# combined.net
KiCad netlist of a schematic drawn in EAGLE
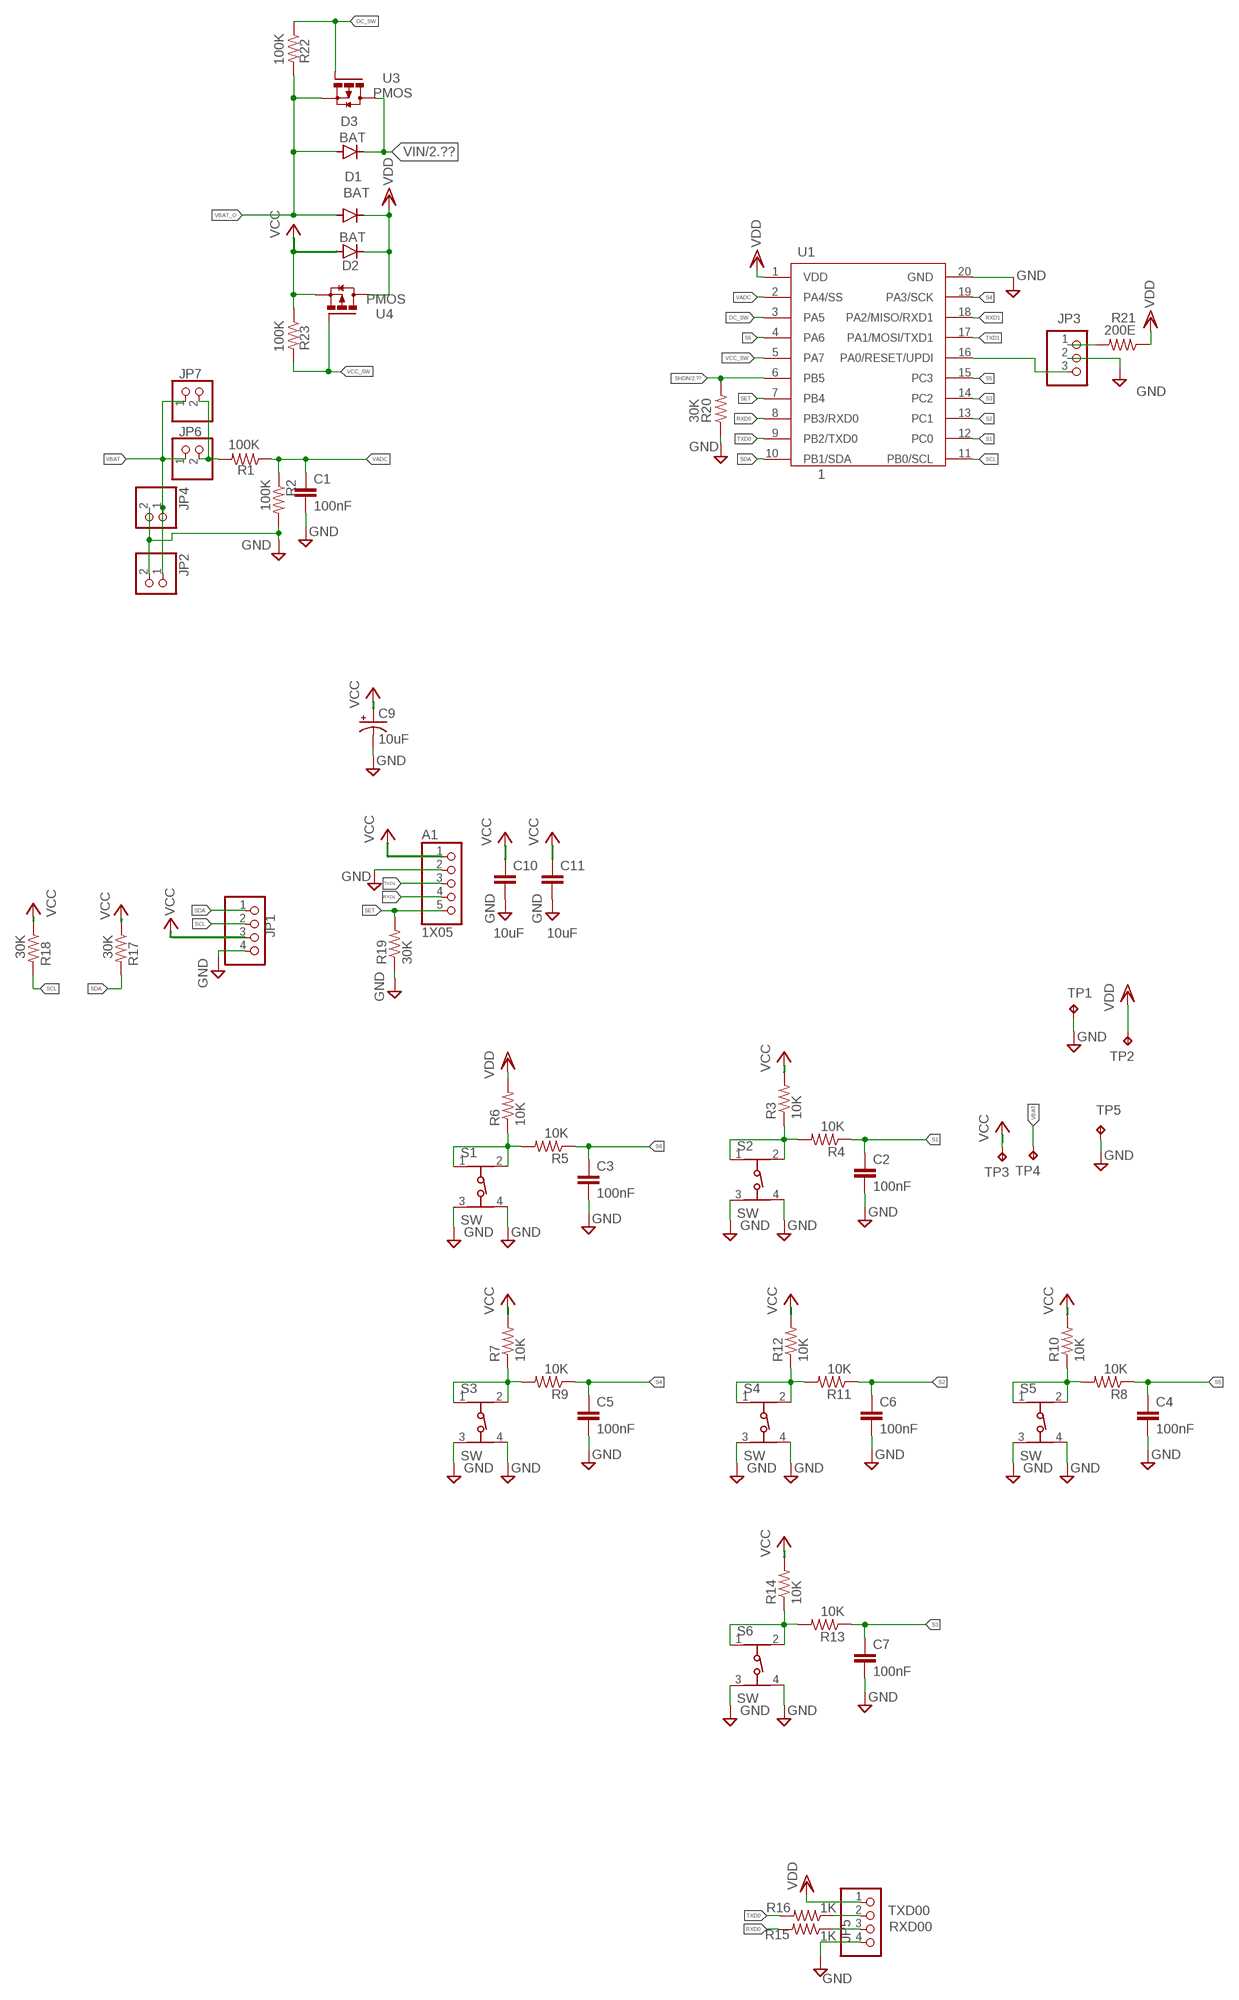
[diagram p0: schematic, sheet 1]
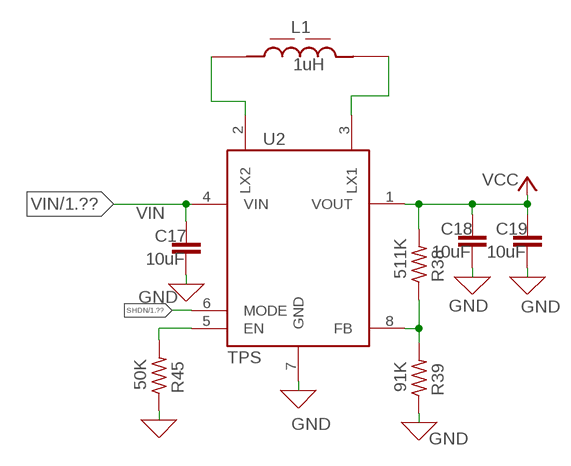
[diagram p1: schematic, sheet 2]

(export (version "E")
  (design (tool "Eeschema 10.0.6"))
  (components
    (comp (ref "C17")
      (value "10uF")
      (footprint "eagle-import:C0805")
      (libsource (lib "eagle-import") (part "C-EUC0805"))
    )
    (comp (ref "C18")
      (value "10uF")
      (footprint "eagle-import:C0805")
      (libsource (lib "eagle-import") (part "C-EUC0805"))
    )
    (comp (ref "C19")
      (value "10uF")
      (footprint "eagle-import:C0805")
      (libsource (lib "eagle-import") (part "C-EUC0805"))
    )
    (comp (ref "L1")
      (value "1uH")
      (footprint "eagle-import:IND_74404043220A")
      (fields (field (name "MF") "Wurth Electronics") (field (name "MP") "74404043220A"))
      (libsource (lib "eagle-import") (part "5040_INDUCTOR"))
    )
    (comp (ref "R38")
      (value "511K")
      (footprint "eagle-import:M0805")
      (libsource (lib "eagle-import") (part "R-US_M0805"))
    )
    (comp (ref "R39")
      (value "91K")
      (footprint "eagle-import:M0805")
      (libsource (lib "eagle-import") (part "R-US_M0805"))
    )
    (comp (ref "R45")
      (value "50K")
      (footprint "eagle-import:M0805")
      (libsource (lib "eagle-import") (part "R-US_M0805"))
    )
    (comp (ref "U2")
      (value "TPS")
      (footprint "eagle-import:SOTFL50P160X60-8N")
      (fields (field (name "MF") "Texas Instruments") (field (name "MP") "TPS563212DRLR"))
      (libsource (lib "eagle-import") (part "TPS563212DRLR"))
    )
    (comp (ref "A1")
      (value "1X05")
      (footprint "eagle-import:1X05X254")
      (libsource (lib "eagle-import") (part "1X05"))
    )
    (comp (ref "C1")
      (value "100nF")
      (footprint "eagle-import:C0805")
      (libsource (lib "eagle-import") (part "C-EUC0805"))
    )
    (comp (ref "C2")
      (value "100nF")
      (footprint "eagle-import:C0805")
      (libsource (lib "eagle-import") (part "C-EUC0805"))
    )
    (comp (ref "C3")
      (value "100nF")
      (footprint "eagle-import:C0805")
      (libsource (lib "eagle-import") (part "C-EUC0805"))
    )
    (comp (ref "C4")
      (value "100nF")
      (footprint "eagle-import:C0805")
      (libsource (lib "eagle-import") (part "C-EUC0805"))
    )
    (comp (ref "C5")
      (value "100nF")
      (footprint "eagle-import:C0805")
      (libsource (lib "eagle-import") (part "C-EUC0805"))
    )
    (comp (ref "C6")
      (value "100nF")
      (footprint "eagle-import:C0805")
      (libsource (lib "eagle-import") (part "C-EUC0805"))
    )
    (comp (ref "C7")
      (value "100nF")
      (footprint "eagle-import:C0805")
      (libsource (lib "eagle-import") (part "C-EUC0805"))
    )
    (comp (ref "C9")
      (value "10uF")
      (footprint "eagle-import:CT3528")
      (libsource (lib "eagle-import") (part "CPOL-USCT3528"))
    )
    (comp (ref "C10")
      (value "10uF")
      (footprint "eagle-import:C0805")
      (libsource (lib "eagle-import") (part "C-EUC0805"))
    )
    (comp (ref "C11")
      (value "10uF")
      (footprint "eagle-import:C0805")
      (libsource (lib "eagle-import") (part "C-EUC0805"))
    )
    (comp (ref "D1")
      (value "BAT")
      (footprint "eagle-import:SOD-123_MINI-SMA")
      (libsource (lib "eagle-import") (part "CGRM400-G5"))
    )
    (comp (ref "D2")
      (value "BAT")
      (footprint "eagle-import:SOD-123_MINI-SMA")
      (libsource (lib "eagle-import") (part "CGRM400-G5"))
    )
    (comp (ref "D3")
      (value "BAT")
      (footprint "eagle-import:SOD-123_MINI-SMA")
      (libsource (lib "eagle-import") (part "CGRM400-G5"))
    )
    (comp (ref "JP1")
      (value "PINHD-1X04_2.54-S")
      (footprint "eagle-import:1X04-S")
      (libsource (lib "eagle-import") (part "PINHD-1X04_2.54-S"))
    )
    (comp (ref "JP2")
      (value "PINHD-1X02_2.54-S")
      (footprint "eagle-import:1X02-S")
      (libsource (lib "eagle-import") (part "PINHD-1X02_2.54-S"))
    )
    (comp (ref "JP3")
      (value "PINHD-1X03_2.54-S")
      (footprint "eagle-import:1X03-S")
      (libsource (lib "eagle-import") (part "PINHD-1X03_2.54-S"))
    )
    (comp (ref "JP4")
      (value "PINHD-1X02_2.54-S")
      (footprint "eagle-import:1X02-S")
      (libsource (lib "eagle-import") (part "PINHD-1X02_2.54-S"))
    )
    (comp (ref "JP5")
      (value "PINHD-1X04_2.54-S")
      (footprint "eagle-import:1X04-S")
      (libsource (lib "eagle-import") (part "PINHD-1X04_2.54-S"))
    )
    (comp (ref "JP6")
      (value "PINHD-1X02_2.54-S")
      (footprint "eagle-import:1X02-S")
      (libsource (lib "eagle-import") (part "PINHD-1X02_2.54-S"))
    )
    (comp (ref "JP7")
      (value "PINHD-1X02_2.54-S")
      (footprint "eagle-import:1X02-S")
      (libsource (lib "eagle-import") (part "PINHD-1X02_2.54-S"))
    )
    (comp (ref "R1")
      (value "100K")
      (footprint "eagle-import:R0805")
      (libsource (lib "eagle-import") (part "R-US_R0805"))
    )
    (comp (ref "R2")
      (value "100K")
      (footprint "eagle-import:R0805")
      (libsource (lib "eagle-import") (part "R-US_R0805"))
    )
    (comp (ref "R3")
      (value "10K")
      (footprint "eagle-import:R0805")
      (libsource (lib "eagle-import") (part "R-US_R0805"))
    )
    (comp (ref "R4")
      (value "10K")
      (footprint "eagle-import:R0805")
      (libsource (lib "eagle-import") (part "R-US_R0805"))
    )
    (comp (ref "R5")
      (value "10K")
      (footprint "eagle-import:R0805")
      (libsource (lib "eagle-import") (part "R-US_R0805"))
    )
    (comp (ref "R6")
      (value "10K")
      (footprint "eagle-import:R0805")
      (libsource (lib "eagle-import") (part "R-US_R0805"))
    )
    (comp (ref "R7")
      (value "10K")
      (footprint "eagle-import:R0805")
      (libsource (lib "eagle-import") (part "R-US_R0805"))
    )
    (comp (ref "R8")
      (value "10K")
      (footprint "eagle-import:R0805")
      (libsource (lib "eagle-import") (part "R-US_R0805"))
    )
    (comp (ref "R9")
      (value "10K")
      (footprint "eagle-import:R0805")
      (libsource (lib "eagle-import") (part "R-US_R0805"))
    )
    (comp (ref "R10")
      (value "10K")
      (footprint "eagle-import:R0805")
      (libsource (lib "eagle-import") (part "R-US_R0805"))
    )
    (comp (ref "R11")
      (value "10K")
      (footprint "eagle-import:R0805")
      (libsource (lib "eagle-import") (part "R-US_R0805"))
    )
    (comp (ref "R12")
      (value "10K")
      (footprint "eagle-import:R0805")
      (libsource (lib "eagle-import") (part "R-US_R0805"))
    )
    (comp (ref "R13")
      (value "10K")
      (footprint "eagle-import:R0805")
      (libsource (lib "eagle-import") (part "R-US_R0805"))
    )
    (comp (ref "R14")
      (value "10K")
      (footprint "eagle-import:R0805")
      (libsource (lib "eagle-import") (part "R-US_R0805"))
    )
    (comp (ref "R15")
      (value "1K")
      (footprint "eagle-import:R0805")
      (libsource (lib "eagle-import") (part "R-US_R0805"))
    )
    (comp (ref "R16")
      (value "1K")
      (footprint "eagle-import:R0805")
      (libsource (lib "eagle-import") (part "R-US_R0805"))
    )
    (comp (ref "R17")
      (value "30K")
      (footprint "eagle-import:R0805")
      (libsource (lib "eagle-import") (part "R-US_R0805"))
    )
    (comp (ref "R18")
      (value "30K")
      (footprint "eagle-import:R0805")
      (libsource (lib "eagle-import") (part "R-US_R0805"))
    )
    (comp (ref "R19")
      (value "30K")
      (footprint "eagle-import:R0805")
      (libsource (lib "eagle-import") (part "R-US_R0805"))
    )
    (comp (ref "R20")
      (value "30K")
      (footprint "eagle-import:R0805")
      (libsource (lib "eagle-import") (part "R-US_R0805"))
    )
    (comp (ref "R21")
      (value "200E")
      (footprint "eagle-import:R0805")
      (libsource (lib "eagle-import") (part "R-US_R0805"))
    )
    (comp (ref "R22")
      (value "100K")
      (footprint "eagle-import:R0805")
      (libsource (lib "eagle-import") (part "R-US_R0805"))
    )
    (comp (ref "R23")
      (value "100K")
      (footprint "eagle-import:R0805")
      (libsource (lib "eagle-import") (part "R-US_R0805"))
    )
    (comp (ref "S1")
      (value "SW")
      (footprint "eagle-import:SW_55MM")
      (fields (field (name "MF") "C&K") (field (name "MP") "PTS 647 SK38 SMTR2 LFS"))
      (libsource (lib "eagle-import") (part "SW_55MM"))
    )
    (comp (ref "S2")
      (value "SW")
      (footprint "eagle-import:SW_55MM")
      (fields (field (name "MF") "C&K") (field (name "MP") "PTS 647 SK38 SMTR2 LFS"))
      (libsource (lib "eagle-import") (part "SW_55MM"))
    )
    (comp (ref "S3")
      (value "SW")
      (footprint "eagle-import:SW_55MM")
      (fields (field (name "MF") "C&K") (field (name "MP") "PTS 647 SK38 SMTR2 LFS"))
      (libsource (lib "eagle-import") (part "SW_55MM"))
    )
    (comp (ref "S4")
      (value "SW")
      (footprint "eagle-import:SW_55MM")
      (fields (field (name "MF") "C&K") (field (name "MP") "PTS 647 SK38 SMTR2 LFS"))
      (libsource (lib "eagle-import") (part "SW_55MM"))
    )
    (comp (ref "S5")
      (value "SW")
      (footprint "eagle-import:SW_55MM")
      (fields (field (name "MF") "C&K") (field (name "MP") "PTS 647 SK38 SMTR2 LFS"))
      (libsource (lib "eagle-import") (part "SW_55MM"))
    )
    (comp (ref "S6")
      (value "SW")
      (footprint "eagle-import:SW_55MM")
      (fields (field (name "MF") "C&K") (field (name "MP") "PTS 647 SK38 SMTR2 LFS"))
      (libsource (lib "eagle-import") (part "SW_55MM"))
    )
    (comp (ref "TP1")
      (value "GND")
      (footprint "eagle-import:TP18R")
      (libsource (lib "eagle-import") (part "TPTP18R"))
    )
    (comp (ref "TP2")
      (value "VDD")
      (footprint "eagle-import:TP18R")
      (libsource (lib "eagle-import") (part "TPTP18R"))
    )
    (comp (ref "TP3")
      (value "VCC")
      (footprint "eagle-import:TP18R")
      (libsource (lib "eagle-import") (part "TPTP18R"))
    )
    (comp (ref "TP4")
      (value "VBAT")
      (footprint "eagle-import:TP18R")
      (libsource (lib "eagle-import") (part "TPTP18R"))
    )
    (comp (ref "TP5")
      (value "GND")
      (footprint "eagle-import:TP18R")
      (libsource (lib "eagle-import") (part "TPTP18R"))
    )
    (comp (ref "U1")
      (value "1")
      (footprint "eagle-import:SOIC127P1032X265-20N")
      (fields (field (name "MF") "Microchip Technology") (field (name "MP") "ATTINY1616-SNR"))
      (libsource (lib "eagle-import") (part "ATTINY1616-SNR"))
    )
    (comp (ref "U3")
      (value "PMOS")
      (footprint "eagle-import:SOT103P240X110-3N")
      (fields (field (name "MF") "Diodes Inc.") (field (name "MP") "DMP3130L-7"))
      (libsource (lib "eagle-import") (part "DMP3165L"))
    )
    (comp (ref "U4")
      (value "PMOS")
      (footprint "eagle-import:SOT103P240X110-3N")
      (fields (field (name "MF") "Diodes Inc.") (field (name "MP") "DMP3130L-7"))
      (libsource (lib "eagle-import") (part "DMP3165L"))
    )
  )
  (nets
    (net (code "1") (name "DC_SW") (class "Default")
      (node (ref "R22") (pin "1") (pinfunction "1_1") (pintype "passive"))
      (node (ref "U1") (pin "3") (pinfunction "PA5_3") (pintype "bidirectional"))
      (node (ref "U3") (pin "1") (pinfunction "G_1") (pintype "passive"))
    )
    (net (code "2") (name "GND") (class "Default")
      (node (ref "A1") (pin "2") (pinfunction "2_2") (pintype "passive"))
      (node (ref "C1") (pin "2") (pinfunction "2_2") (pintype "passive"))
      (node (ref "C10") (pin "2") (pinfunction "2_2") (pintype "passive"))
      (node (ref "C11") (pin "2") (pinfunction "2_2") (pintype "passive"))
      (node (ref "C17") (pin "2") (pinfunction "2_2") (pintype "passive"))
      (node (ref "C18") (pin "2") (pinfunction "2_2") (pintype "passive"))
      (node (ref "C19") (pin "2") (pinfunction "2_2") (pintype "passive"))
      (node (ref "C2") (pin "2") (pinfunction "2_2") (pintype "passive"))
      (node (ref "C3") (pin "2") (pinfunction "2_2") (pintype "passive"))
      (node (ref "C4") (pin "2") (pinfunction "2_2") (pintype "passive"))
      (node (ref "C5") (pin "2") (pinfunction "2_2") (pintype "passive"))
      (node (ref "C6") (pin "2") (pinfunction "2_2") (pintype "passive"))
      (node (ref "C7") (pin "2") (pinfunction "2_2") (pintype "passive"))
      (node (ref "C9") (pin "-") (pinfunction "-_-") (pintype "passive"))
      (node (ref "JP1") (pin "4") (pinfunction "4_4") (pintype "passive"))
      (node (ref "JP2") (pin "2") (pinfunction "2_2") (pintype "passive"))
      (node (ref "JP3") (pin "2") (pinfunction "2_2") (pintype "passive"))
      (node (ref "JP4") (pin "2") (pinfunction "2_2") (pintype "passive"))
      (node (ref "JP5") (pin "4") (pinfunction "4_4") (pintype "passive"))
      (node (ref "R19") (pin "1") (pinfunction "1_1") (pintype "passive"))
      (node (ref "R2") (pin "2") (pinfunction "2_2") (pintype "passive"))
      (node (ref "R20") (pin "1") (pinfunction "1_1") (pintype "passive"))
      (node (ref "R39") (pin "1") (pinfunction "1_1") (pintype "passive"))
      (node (ref "R45") (pin "1") (pinfunction "1_1") (pintype "passive"))
      (node (ref "S1") (pin "3") (pinfunction "3_3") (pintype "passive"))
      (node (ref "S1") (pin "4") (pinfunction "4_4") (pintype "passive"))
      (node (ref "S2") (pin "3") (pinfunction "3_3") (pintype "passive"))
      (node (ref "S2") (pin "4") (pinfunction "4_4") (pintype "passive"))
      (node (ref "S3") (pin "3") (pinfunction "3_3") (pintype "passive"))
      (node (ref "S3") (pin "4") (pinfunction "4_4") (pintype "passive"))
      (node (ref "S4") (pin "3") (pinfunction "3_3") (pintype "passive"))
      (node (ref "S4") (pin "4") (pinfunction "4_4") (pintype "passive"))
      (node (ref "S5") (pin "3") (pinfunction "3_3") (pintype "passive"))
      (node (ref "S5") (pin "4") (pinfunction "4_4") (pintype "passive"))
      (node (ref "S6") (pin "3") (pinfunction "3_3") (pintype "passive"))
      (node (ref "S6") (pin "4") (pinfunction "4_4") (pintype "passive"))
      (node (ref "TP1") (pin "TP") (pinfunction "TP_TP") (pintype "input"))
      (node (ref "TP5") (pin "TP") (pinfunction "TP_TP") (pintype "input"))
      (node (ref "U1") (pin "20") (pinfunction "GND_20") (pintype "power_in"))
      (node (ref "U2") (pin "7") (pinfunction "GND_7") (pintype "power_in"))
    )
    (net (code "3") (name "Net-(JP3-Pad1)") (class "Default")
      (node (ref "JP3") (pin "1") (pinfunction "1_1") (pintype "passive"))
      (node (ref "R21") (pin "2") (pinfunction "2_2") (pintype "passive"))
    )
    (net (code "4") (name "Net-(R3-Pad1)") (class "Default")
      (node (ref "R3") (pin "1") (pinfunction "1_1") (pintype "passive"))
      (node (ref "R4") (pin "2") (pinfunction "2_2") (pintype "passive"))
      (node (ref "S2") (pin "1") (pinfunction "1_1") (pintype "passive"))
      (node (ref "S2") (pin "2") (pinfunction "2_2") (pintype "passive"))
    )
    (net (code "5") (name "Net-(R5-Pad2)") (class "Default")
      (node (ref "R5") (pin "2") (pinfunction "2_2") (pintype "passive"))
      (node (ref "R6") (pin "1") (pinfunction "1_1") (pintype "passive"))
      (node (ref "S1") (pin "1") (pinfunction "1_1") (pintype "passive"))
      (node (ref "S1") (pin "2") (pinfunction "2_2") (pintype "passive"))
    )
    (net (code "6") (name "Net-(R7-Pad1)") (class "Default")
      (node (ref "R7") (pin "1") (pinfunction "1_1") (pintype "passive"))
      (node (ref "R9") (pin "2") (pinfunction "2_2") (pintype "passive"))
      (node (ref "S3") (pin "1") (pinfunction "1_1") (pintype "passive"))
      (node (ref "S3") (pin "2") (pinfunction "2_2") (pintype "passive"))
    )
    (net (code "7") (name "Net-(R10-Pad1)") (class "Default")
      (node (ref "R10") (pin "1") (pinfunction "1_1") (pintype "passive"))
      (node (ref "R8") (pin "2") (pinfunction "2_2") (pintype "passive"))
      (node (ref "S5") (pin "1") (pinfunction "1_1") (pintype "passive"))
      (node (ref "S5") (pin "2") (pinfunction "2_2") (pintype "passive"))
    )
    (net (code "8") (name "Net-(R11-Pad2)") (class "Default")
      (node (ref "R11") (pin "2") (pinfunction "2_2") (pintype "passive"))
      (node (ref "R12") (pin "1") (pinfunction "1_1") (pintype "passive"))
      (node (ref "S4") (pin "1") (pinfunction "1_1") (pintype "passive"))
      (node (ref "S4") (pin "2") (pinfunction "2_2") (pintype "passive"))
    )
    (net (code "9") (name "Net-(R13-Pad2)") (class "Default")
      (node (ref "R13") (pin "2") (pinfunction "2_2") (pintype "passive"))
      (node (ref "R14") (pin "1") (pinfunction "1_1") (pintype "passive"))
      (node (ref "S6") (pin "1") (pinfunction "1_1") (pintype "passive"))
      (node (ref "S6") (pin "2") (pinfunction "2_2") (pintype "passive"))
    )
    (net (code "10") (name "Net-(U1-PA0{slash}RESET{slash}UPDI)") (class "Default")
      (node (ref "JP3") (pin "3") (pinfunction "3_3") (pintype "passive"))
      (node (ref "U1") (pin "16") (pinfunction "PA0/RESET/UPDI_16") (pintype "bidirectional"))
    )
    (net (code "11") (name "Net-(U2-EN)") (class "Default")
      (node (ref "R45") (pin "2") (pinfunction "2_2") (pintype "passive"))
      (node (ref "U2") (pin "5") (pinfunction "EN_5") (pintype "bidirectional"))
    )
    (net (code "12") (name "Net-(U2-FB)") (class "Default")
      (node (ref "R38") (pin "1") (pinfunction "1_1") (pintype "passive"))
      (node (ref "R39") (pin "2") (pinfunction "2_2") (pintype "passive"))
      (node (ref "U2") (pin "8") (pinfunction "FB_8") (pintype "input"))
    )
    (net (code "13") (name "Net-(U2-LX1)") (class "Default")
      (node (ref "L1") (pin "2") (pinfunction "2_2") (pintype "passive"))
      (node (ref "U2") (pin "3") (pinfunction "LX1_3") (pintype "output"))
    )
    (net (code "14") (name "Net-(U2-LX2)") (class "Default")
      (node (ref "L1") (pin "1") (pinfunction "1_1") (pintype "passive"))
      (node (ref "U2") (pin "2") (pinfunction "LX2_2") (pintype "input"))
    )
    (net (code "15") (name "RXD0") (class "Default")
      (node (ref "R15") (pin "2") (pinfunction "2_2") (pintype "passive"))
      (node (ref "U1") (pin "8") (pinfunction "PB3/RXD0_8") (pintype "bidirectional"))
    )
    (net (code "16") (name "RXD00") (class "Default")
      (node (ref "JP5") (pin "3") (pinfunction "3_3") (pintype "passive"))
      (node (ref "R15") (pin "1") (pinfunction "1_1") (pintype "passive"))
    )
    (net (code "17") (name "RXD1") (class "Default")
      (node (ref "A1") (pin "4") (pinfunction "4_4") (pintype "passive"))
      (node (ref "U1") (pin "18") (pinfunction "PA2/MISO/RXD1_18") (pintype "bidirectional"))
    )
    (net (code "18") (name "S1") (class "Default")
      (node (ref "C2") (pin "1") (pinfunction "1_1") (pintype "passive"))
      (node (ref "R4") (pin "1") (pinfunction "1_1") (pintype "passive"))
      (node (ref "U1") (pin "12") (pinfunction "PC0_12") (pintype "bidirectional"))
    )
    (net (code "19") (name "S2") (class "Default")
      (node (ref "C6") (pin "1") (pinfunction "1_1") (pintype "passive"))
      (node (ref "R11") (pin "1") (pinfunction "1_1") (pintype "passive"))
      (node (ref "U1") (pin "13") (pinfunction "PC1_13") (pintype "bidirectional"))
    )
    (net (code "20") (name "S3") (class "Default")
      (node (ref "C7") (pin "1") (pinfunction "1_1") (pintype "passive"))
      (node (ref "R13") (pin "1") (pinfunction "1_1") (pintype "passive"))
      (node (ref "U1") (pin "14") (pinfunction "PC2_14") (pintype "bidirectional"))
    )
    (net (code "21") (name "S4") (class "Default")
      (node (ref "C5") (pin "1") (pinfunction "1_1") (pintype "passive"))
      (node (ref "R9") (pin "1") (pinfunction "1_1") (pintype "passive"))
      (node (ref "U1") (pin "19") (pinfunction "PA3/SCK_19") (pintype "bidirectional"))
    )
    (net (code "22") (name "S5") (class "Default")
      (node (ref "C4") (pin "1") (pinfunction "1_1") (pintype "passive"))
      (node (ref "R8") (pin "1") (pinfunction "1_1") (pintype "passive"))
      (node (ref "U1") (pin "15") (pinfunction "PC3_15") (pintype "bidirectional"))
    )
    (net (code "23") (name "S6") (class "Default")
      (node (ref "C3") (pin "1") (pinfunction "1_1") (pintype "passive"))
      (node (ref "R5") (pin "1") (pinfunction "1_1") (pintype "passive"))
      (node (ref "U1") (pin "4") (pinfunction "PA6_4") (pintype "bidirectional"))
    )
    (net (code "24") (name "SCL") (class "Default")
      (node (ref "JP1") (pin "2") (pinfunction "2_2") (pintype "passive"))
      (node (ref "R18") (pin "2") (pinfunction "2_2") (pintype "passive"))
      (node (ref "U1") (pin "11") (pinfunction "PB0/SCL_11") (pintype "bidirectional"))
    )
    (net (code "25") (name "SDA") (class "Default")
      (node (ref "JP1") (pin "1") (pinfunction "1_1") (pintype "passive"))
      (node (ref "R17") (pin "2") (pinfunction "2_2") (pintype "passive"))
      (node (ref "U1") (pin "10") (pinfunction "PB1/SDA_10") (pintype "bidirectional"))
    )
    (net (code "26") (name "SET") (class "Default")
      (node (ref "A1") (pin "5") (pinfunction "5_5") (pintype "passive"))
      (node (ref "R19") (pin "2") (pinfunction "2_2") (pintype "passive"))
      (node (ref "U1") (pin "7") (pinfunction "PB4_7") (pintype "bidirectional"))
    )
    (net (code "27") (name "SHDN") (class "Default")
      (node (ref "R20") (pin "2") (pinfunction "2_2") (pintype "passive"))
      (node (ref "U1") (pin "6") (pinfunction "PB5_6") (pintype "bidirectional"))
      (node (ref "U2") (pin "6") (pinfunction "MODE_6") (pintype "bidirectional"))
    )
    (net (code "28") (name "TXD0") (class "Default")
      (node (ref "R16") (pin "2") (pinfunction "2_2") (pintype "passive"))
      (node (ref "U1") (pin "9") (pinfunction "PB2/TXD0_9") (pintype "bidirectional"))
    )
    (net (code "29") (name "TXD00") (class "Default")
      (node (ref "JP5") (pin "2") (pinfunction "2_2") (pintype "passive"))
      (node (ref "R16") (pin "1") (pinfunction "1_1") (pintype "passive"))
    )
    (net (code "30") (name "TXD1") (class "Default")
      (node (ref "A1") (pin "3") (pinfunction "3_3") (pintype "passive"))
      (node (ref "U1") (pin "17") (pinfunction "PA1/MOSI/TXD1_17") (pintype "bidirectional"))
    )
    (net (code "31") (name "VADC") (class "Default")
      (node (ref "C1") (pin "1") (pinfunction "1_1") (pintype "passive"))
      (node (ref "R1") (pin "1") (pinfunction "1_1") (pintype "passive"))
      (node (ref "R2") (pin "1") (pinfunction "1_1") (pintype "passive"))
      (node (ref "U1") (pin "2") (pinfunction "PA4/SS_2") (pintype "bidirectional"))
    )
    (net (code "32") (name "VBAT") (class "Default")
      (node (ref "JP2") (pin "1") (pinfunction "1_1") (pintype "passive"))
      (node (ref "JP4") (pin "1") (pinfunction "1_1") (pintype "passive"))
      (node (ref "JP6") (pin "1") (pinfunction "1_1") (pintype "passive"))
      (node (ref "JP7") (pin "1") (pinfunction "1_1") (pintype "passive"))
      (node (ref "TP4") (pin "TP") (pinfunction "TP_TP") (pintype "input"))
    )
    (net (code "33") (name "VBAT_O") (class "Default")
      (node (ref "D1") (pin "A") (pinfunction "A_A") (pintype "passive"))
      (node (ref "D3") (pin "A") (pinfunction "A_A") (pintype "passive"))
      (node (ref "JP6") (pin "2") (pinfunction "2_2") (pintype "passive"))
      (node (ref "JP7") (pin "2") (pinfunction "2_2") (pintype "passive"))
      (node (ref "R1") (pin "2") (pinfunction "2_2") (pintype "passive"))
      (node (ref "R22") (pin "2") (pinfunction "2_2") (pintype "passive"))
      (node (ref "U3") (pin "2") (pinfunction "S_2") (pintype "passive"))
    )
    (net (code "34") (name "VCC") (class "Default")
      (node (ref "A1") (pin "1") (pinfunction "1_1") (pintype "passive"))
      (node (ref "C10") (pin "1") (pinfunction "1_1") (pintype "passive"))
      (node (ref "C11") (pin "1") (pinfunction "1_1") (pintype "passive"))
      (node (ref "C18") (pin "1") (pinfunction "1_1") (pintype "passive"))
      (node (ref "C19") (pin "1") (pinfunction "1_1") (pintype "passive"))
      (node (ref "C9") (pin "+") (pinfunction "+_+") (pintype "passive"))
      (node (ref "D2") (pin "A") (pinfunction "A_A") (pintype "passive"))
      (node (ref "JP1") (pin "3") (pinfunction "3_3") (pintype "passive"))
      (node (ref "R10") (pin "2") (pinfunction "2_2") (pintype "passive"))
      (node (ref "R12") (pin "2") (pinfunction "2_2") (pintype "passive"))
      (node (ref "R14") (pin "2") (pinfunction "2_2") (pintype "passive"))
      (node (ref "R17") (pin "1") (pinfunction "1_1") (pintype "passive"))
      (node (ref "R18") (pin "1") (pinfunction "1_1") (pintype "passive"))
      (node (ref "R23") (pin "1") (pinfunction "1_1") (pintype "passive"))
      (node (ref "R3") (pin "2") (pinfunction "2_2") (pintype "passive"))
      (node (ref "R38") (pin "2") (pinfunction "2_2") (pintype "passive"))
      (node (ref "R7") (pin "2") (pinfunction "2_2") (pintype "passive"))
      (node (ref "TP3") (pin "TP") (pinfunction "TP_TP") (pintype "input"))
      (node (ref "U2") (pin "1") (pinfunction "VOUT_1") (pintype "bidirectional"))
      (node (ref "U4") (pin "2") (pinfunction "S_2") (pintype "passive"))
    )
    (net (code "35") (name "VCC_SW") (class "Default")
      (node (ref "R23") (pin "2") (pinfunction "2_2") (pintype "passive"))
      (node (ref "U1") (pin "5") (pinfunction "PA7_5") (pintype "bidirectional"))
      (node (ref "U4") (pin "1") (pinfunction "G_1") (pintype "passive"))
    )
    (net (code "36") (name "VDD") (class "Default")
      (node (ref "D1") (pin "C") (pinfunction "C_C") (pintype "passive"))
      (node (ref "D2") (pin "C") (pinfunction "C_C") (pintype "passive"))
      (node (ref "JP5") (pin "1") (pinfunction "1_1") (pintype "passive"))
      (node (ref "R21") (pin "1") (pinfunction "1_1") (pintype "passive"))
      (node (ref "R6") (pin "2") (pinfunction "2_2") (pintype "passive"))
      (node (ref "TP2") (pin "TP") (pinfunction "TP_TP") (pintype "input"))
      (node (ref "U1") (pin "1") (pinfunction "VDD_1") (pintype "power_in"))
      (node (ref "U4") (pin "3") (pinfunction "D_3") (pintype "passive"))
    )
    (net (code "37") (name "VIN") (class "Default")
      (node (ref "C17") (pin "1") (pinfunction "1_1") (pintype "passive"))
      (node (ref "D3") (pin "C") (pinfunction "C_C") (pintype "passive"))
      (node (ref "U2") (pin "4") (pinfunction "VIN_4") (pintype "input"))
      (node (ref "U3") (pin "3") (pinfunction "D_3") (pintype "passive"))
    )
  )
)
